# dds.net
KiCad netlist of a schematic drawn in EAGLE
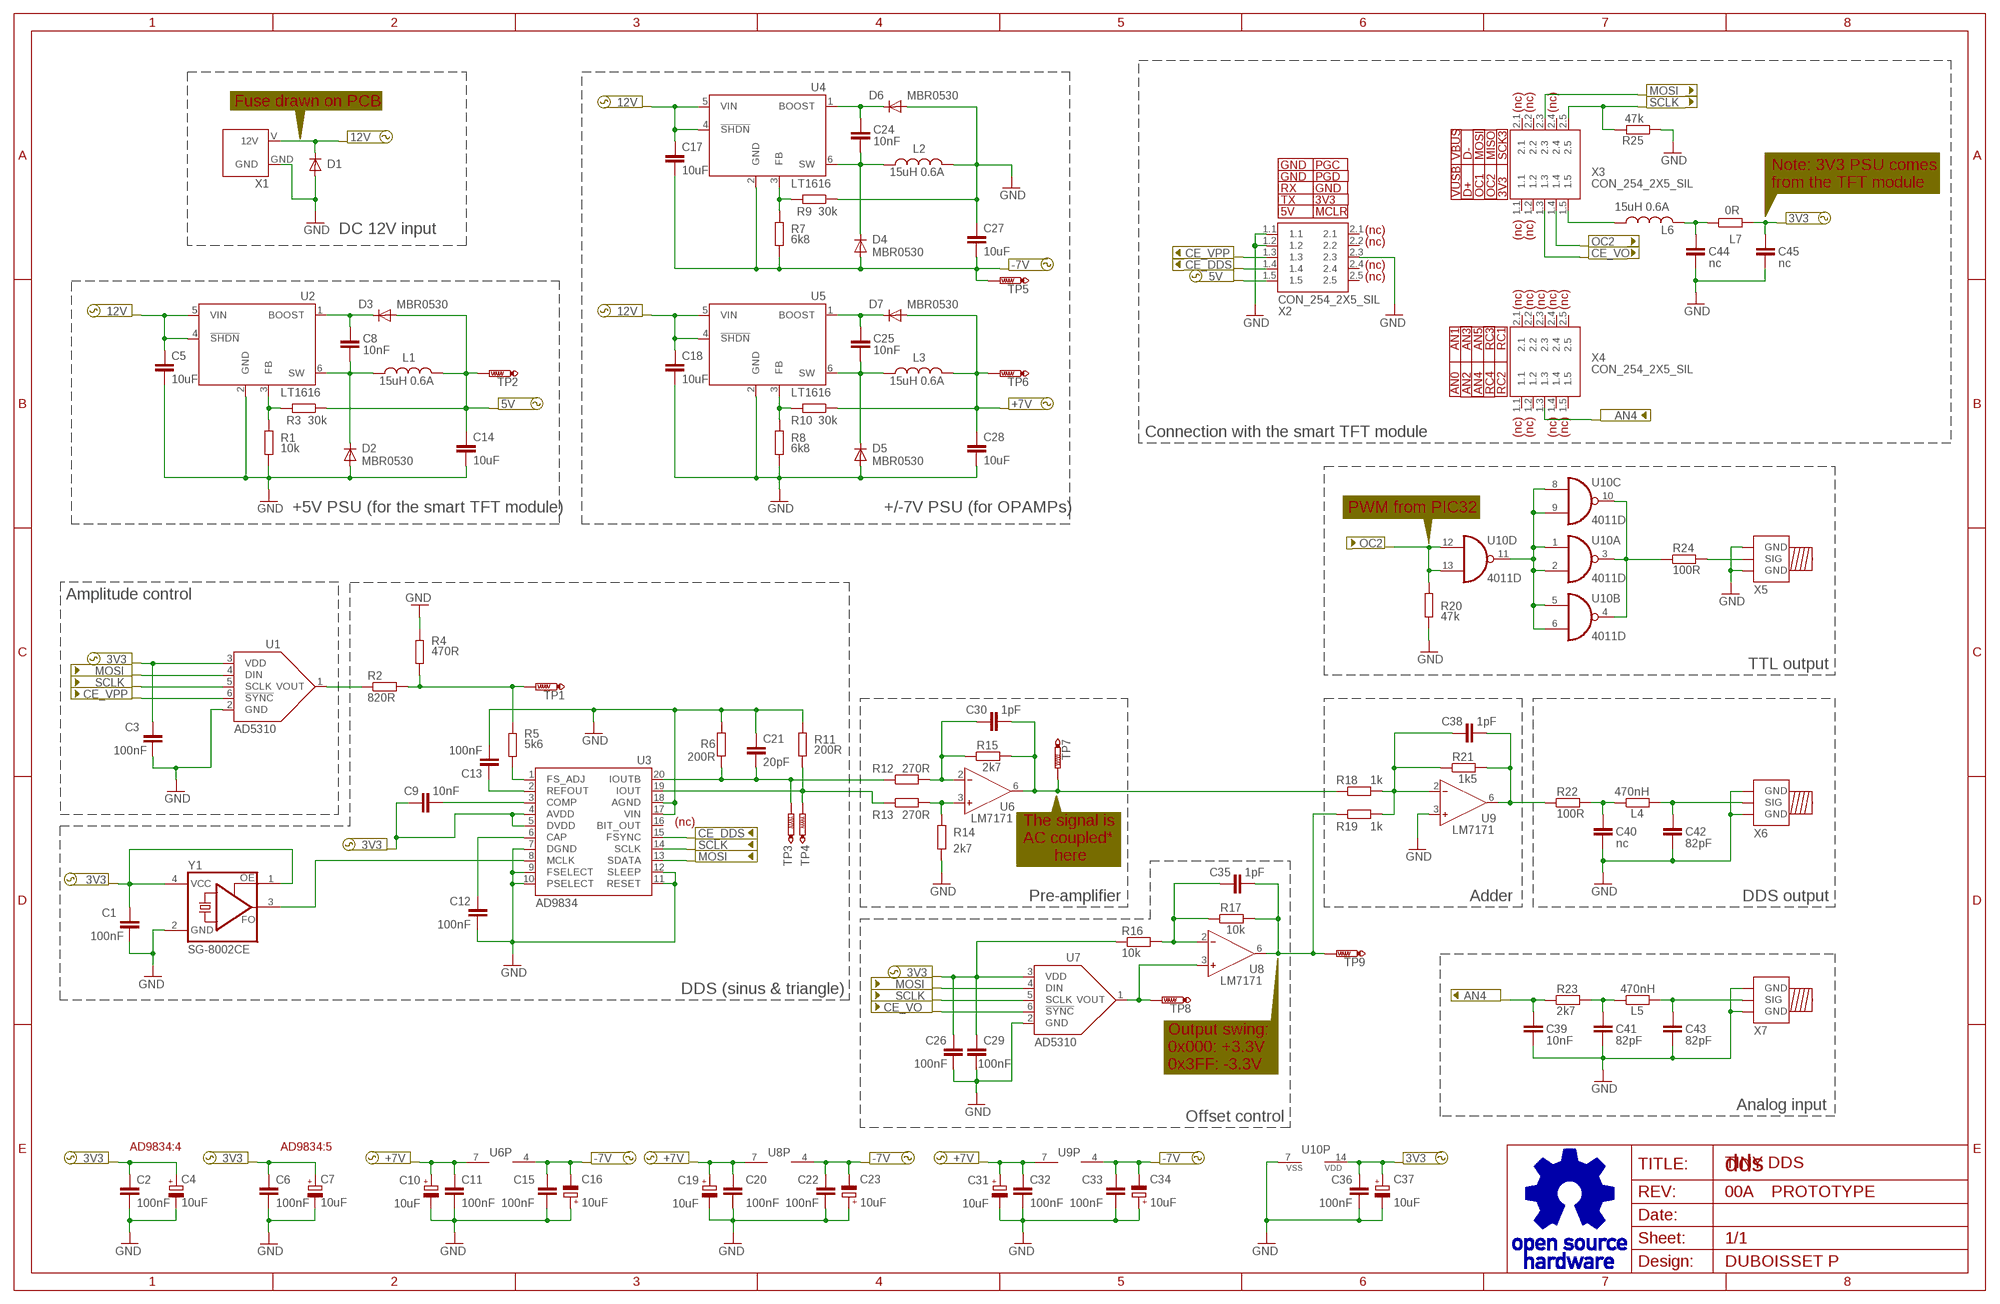
[diagram p0: schematic, sheet 1]

(export (version "E")
  (design (tool "Eeschema 10.0.6"))
  (components
    (comp (ref "C1")
      (value "100nF")
      (footprint "eagle-import:C0603")
      (libsource (lib "eagle-import") (part "C-EUC0603"))
    )
    (comp (ref "C2")
      (value "100nF")
      (footprint "eagle-import:C0603")
      (libsource (lib "eagle-import") (part "C-EUC0603"))
    )
    (comp (ref "C3")
      (value "100nF")
      (footprint "eagle-import:C0603")
      (libsource (lib "eagle-import") (part "C-EUC0603"))
    )
    (comp (ref "C4")
      (value "10uF")
      (footprint "eagle-import:SMC_B")
      (libsource (lib "eagle-import") (part "CPOL-EUSMCB"))
    )
    (comp (ref "C5")
      (value "10uF")
      (footprint "eagle-import:C0805")
      (libsource (lib "eagle-import") (part "C-EUC0805"))
    )
    (comp (ref "C6")
      (value "100nF")
      (footprint "eagle-import:C0603")
      (libsource (lib "eagle-import") (part "C-EUC0603"))
    )
    (comp (ref "C7")
      (value "10uF")
      (footprint "eagle-import:SMC_B")
      (libsource (lib "eagle-import") (part "CPOL-EUSMCB"))
    )
    (comp (ref "C8")
      (value "10nF")
      (footprint "eagle-import:C0603")
      (libsource (lib "eagle-import") (part "C-EUC0603"))
    )
    (comp (ref "C9")
      (value "10nF")
      (footprint "eagle-import:C0603")
      (libsource (lib "eagle-import") (part "C-EUC0603"))
    )
    (comp (ref "C10")
      (value "10uF")
      (footprint "eagle-import:SMC_B")
      (libsource (lib "eagle-import") (part "CPOL-EUSMCB"))
    )
    (comp (ref "C11")
      (value "100nF")
      (footprint "eagle-import:C0603")
      (libsource (lib "eagle-import") (part "C-EUC0603"))
    )
    (comp (ref "C12")
      (value "100nF")
      (footprint "eagle-import:C0603")
      (libsource (lib "eagle-import") (part "C-EUC0603"))
    )
    (comp (ref "C13")
      (value "100nF")
      (footprint "eagle-import:C0603")
      (libsource (lib "eagle-import") (part "C-EUC0603"))
    )
    (comp (ref "C14")
      (value "10uF")
      (footprint "eagle-import:C0805")
      (libsource (lib "eagle-import") (part "C-EUC0805"))
    )
    (comp (ref "C15")
      (value "100nF")
      (footprint "eagle-import:C0603")
      (libsource (lib "eagle-import") (part "C-EUC0603"))
    )
    (comp (ref "C16")
      (value "10uF")
      (footprint "eagle-import:SMC_B")
      (libsource (lib "eagle-import") (part "CPOL-EUSMCB"))
    )
    (comp (ref "C17")
      (value "10uF")
      (footprint "eagle-import:C0805")
      (libsource (lib "eagle-import") (part "C-EUC0805"))
    )
    (comp (ref "C18")
      (value "10uF")
      (footprint "eagle-import:C0805")
      (libsource (lib "eagle-import") (part "C-EUC0805"))
    )
    (comp (ref "C19")
      (value "10uF")
      (footprint "eagle-import:SMC_B")
      (libsource (lib "eagle-import") (part "CPOL-EUSMCB"))
    )
    (comp (ref "C20")
      (value "100nF")
      (footprint "eagle-import:C0603")
      (libsource (lib "eagle-import") (part "C-EUC0603"))
    )
    (comp (ref "C21")
      (value "20pF")
      (footprint "eagle-import:C0603")
      (libsource (lib "eagle-import") (part "C-EUC0603"))
    )
    (comp (ref "C22")
      (value "100nF")
      (footprint "eagle-import:C0603")
      (libsource (lib "eagle-import") (part "C-EUC0603"))
    )
    (comp (ref "C23")
      (value "10uF")
      (footprint "eagle-import:SMC_B")
      (libsource (lib "eagle-import") (part "CPOL-EUSMCB"))
    )
    (comp (ref "C24")
      (value "10nF")
      (footprint "eagle-import:C0603")
      (libsource (lib "eagle-import") (part "C-EUC0603"))
    )
    (comp (ref "C25")
      (value "10nF")
      (footprint "eagle-import:C0603")
      (libsource (lib "eagle-import") (part "C-EUC0603"))
    )
    (comp (ref "C26")
      (value "100nF")
      (footprint "eagle-import:C0603")
      (libsource (lib "eagle-import") (part "C-EUC0603"))
    )
    (comp (ref "C27")
      (value "10uF")
      (footprint "eagle-import:C0805")
      (libsource (lib "eagle-import") (part "C-EUC0805"))
    )
    (comp (ref "C28")
      (value "10uF")
      (footprint "eagle-import:C0805")
      (libsource (lib "eagle-import") (part "C-EUC0805"))
    )
    (comp (ref "C29")
      (value "100nF")
      (footprint "eagle-import:C0603")
      (libsource (lib "eagle-import") (part "C-EUC0603"))
    )
    (comp (ref "C30")
      (value "1pF")
      (footprint "eagle-import:C0603")
      (libsource (lib "eagle-import") (part "C-EUC0603"))
    )
    (comp (ref "C31")
      (value "10uF")
      (footprint "eagle-import:SMC_B")
      (libsource (lib "eagle-import") (part "CPOL-EUSMCB"))
    )
    (comp (ref "C32")
      (value "100nF")
      (footprint "eagle-import:C0603")
      (libsource (lib "eagle-import") (part "C-EUC0603"))
    )
    (comp (ref "C33")
      (value "100nF")
      (footprint "eagle-import:C0603")
      (libsource (lib "eagle-import") (part "C-EUC0603"))
    )
    (comp (ref "C34")
      (value "10uF")
      (footprint "eagle-import:SMC_B")
      (libsource (lib "eagle-import") (part "CPOL-EUSMCB"))
    )
    (comp (ref "C35")
      (value "1pF")
      (footprint "eagle-import:C0603")
      (libsource (lib "eagle-import") (part "C-EUC0603"))
    )
    (comp (ref "C36")
      (value "100nF")
      (footprint "eagle-import:C0603")
      (libsource (lib "eagle-import") (part "C-EUC0603"))
    )
    (comp (ref "C37")
      (value "10uF")
      (footprint "eagle-import:SMC_B")
      (libsource (lib "eagle-import") (part "CPOL-EUSMCB"))
    )
    (comp (ref "C38")
      (value "1pF")
      (footprint "eagle-import:C0603")
      (libsource (lib "eagle-import") (part "C-EUC0603"))
    )
    (comp (ref "C39")
      (value "10nF")
      (footprint "eagle-import:C0603")
      (libsource (lib "eagle-import") (part "C-EUC0603"))
    )
    (comp (ref "C40")
      (value "nc")
      (footprint "eagle-import:C0603")
      (libsource (lib "eagle-import") (part "C-EUC0603"))
    )
    (comp (ref "C41")
      (value "82pF")
      (footprint "eagle-import:C0603")
      (libsource (lib "eagle-import") (part "C-EUC0603"))
    )
    (comp (ref "C42")
      (value "82pF")
      (footprint "eagle-import:C0603")
      (libsource (lib "eagle-import") (part "C-EUC0603"))
    )
    (comp (ref "C43")
      (value "82pF")
      (footprint "eagle-import:C0603")
      (libsource (lib "eagle-import") (part "C-EUC0603"))
    )
    (comp (ref "C44")
      (value "nc")
      (footprint "eagle-import:C0603")
      (libsource (lib "eagle-import") (part "C-EUC0603"))
    )
    (comp (ref "C45")
      (value "nc")
      (footprint "eagle-import:C0603")
      (libsource (lib "eagle-import") (part "C-EUC0603"))
    )
    (comp (ref "D1")
      (value "DIODE-SMB")
      (footprint "eagle-import:SMB")
      (libsource (lib "eagle-import") (part "DIODE-SMB"))
    )
    (comp (ref "D2")
      (value "MBR0530")
      (footprint "eagle-import:SOD123")
      (libsource (lib "eagle-import") (part "DIODE-SOD123"))
    )
    (comp (ref "D3")
      (value "MBR0530")
      (footprint "eagle-import:SOD123")
      (libsource (lib "eagle-import") (part "DIODE-SOD123"))
    )
    (comp (ref "D4")
      (value "MBR0530")
      (footprint "eagle-import:SOD123")
      (libsource (lib "eagle-import") (part "DIODE-SOD123"))
    )
    (comp (ref "D5")
      (value "MBR0530")
      (footprint "eagle-import:SOD123")
      (libsource (lib "eagle-import") (part "DIODE-SOD123"))
    )
    (comp (ref "D6")
      (value "MBR0530")
      (footprint "eagle-import:SOD123")
      (libsource (lib "eagle-import") (part "DIODE-SOD123"))
    )
    (comp (ref "D7")
      (value "MBR0530")
      (footprint "eagle-import:SOD123")
      (libsource (lib "eagle-import") (part "DIODE-SOD123"))
    )
    (comp (ref "L1")
      (value "15uH 0.6A")
      (footprint "eagle-import:L5X3")
      (libsource (lib "eagle-import") (part "L_TDK_15UH"))
    )
    (comp (ref "L2")
      (value "15uH 0.6A")
      (footprint "eagle-import:L5X3")
      (libsource (lib "eagle-import") (part "L_TDK_15UH"))
    )
    (comp (ref "L3")
      (value "15uH 0.6A")
      (footprint "eagle-import:L5X3")
      (libsource (lib "eagle-import") (part "L_TDK_15UH"))
    )
    (comp (ref "L4")
      (value "470nH")
      (footprint "eagle-import:R0603")
      (libsource (lib "eagle-import") (part "R-EU_R0603"))
    )
    (comp (ref "L5")
      (value "470nH")
      (footprint "eagle-import:R0603")
      (libsource (lib "eagle-import") (part "R-EU_R0603"))
    )
    (comp (ref "L6")
      (value "15uH 0.6A")
      (footprint "eagle-import:L5X3")
      (libsource (lib "eagle-import") (part "L_TDK_15UH"))
    )
    (comp (ref "L7")
      (value "0R")
      (footprint "eagle-import:R0603")
      (libsource (lib "eagle-import") (part "R-EU_R0603"))
    )
    (comp (ref "R1")
      (value "10k")
      (footprint "eagle-import:R0603")
      (libsource (lib "eagle-import") (part "R-EU_R0603"))
    )
    (comp (ref "R2")
      (value "820R")
      (footprint "eagle-import:R0603")
      (libsource (lib "eagle-import") (part "R-EU_R0603"))
    )
    (comp (ref "R3")
      (value "30k")
      (footprint "eagle-import:R0603")
      (libsource (lib "eagle-import") (part "R-EU_R0603"))
    )
    (comp (ref "R4")
      (value "470R")
      (footprint "eagle-import:R0603")
      (libsource (lib "eagle-import") (part "R-EU_R0603"))
    )
    (comp (ref "R5")
      (value "5k6")
      (footprint "eagle-import:R0603")
      (libsource (lib "eagle-import") (part "R-EU_R0603"))
    )
    (comp (ref "R6")
      (value "200R")
      (footprint "eagle-import:R0603")
      (libsource (lib "eagle-import") (part "R-EU_R0603"))
    )
    (comp (ref "R7")
      (value "6k8")
      (footprint "eagle-import:R0603")
      (libsource (lib "eagle-import") (part "R-EU_R0603"))
    )
    (comp (ref "R8")
      (value "6k8")
      (footprint "eagle-import:R0603")
      (libsource (lib "eagle-import") (part "R-EU_R0603"))
    )
    (comp (ref "R9")
      (value "30k")
      (footprint "eagle-import:R0603")
      (libsource (lib "eagle-import") (part "R-EU_R0603"))
    )
    (comp (ref "R10")
      (value "30k")
      (footprint "eagle-import:R0603")
      (libsource (lib "eagle-import") (part "R-EU_R0603"))
    )
    (comp (ref "R11")
      (value "200R")
      (footprint "eagle-import:R0603")
      (libsource (lib "eagle-import") (part "R-EU_R0603"))
    )
    (comp (ref "R12")
      (value "270R")
      (footprint "eagle-import:R0603")
      (libsource (lib "eagle-import") (part "R-EU_R0603"))
    )
    (comp (ref "R13")
      (value "270R")
      (footprint "eagle-import:R0603")
      (libsource (lib "eagle-import") (part "R-EU_R0603"))
    )
    (comp (ref "R14")
      (value "2k7")
      (footprint "eagle-import:R0603")
      (libsource (lib "eagle-import") (part "R-EU_R0603"))
    )
    (comp (ref "R15")
      (value "2k7")
      (footprint "eagle-import:R0603")
      (libsource (lib "eagle-import") (part "R-EU_R0603"))
    )
    (comp (ref "R16")
      (value "10k")
      (footprint "eagle-import:R0603")
      (libsource (lib "eagle-import") (part "R-EU_R0603"))
    )
    (comp (ref "R17")
      (value "10k")
      (footprint "eagle-import:R0603")
      (libsource (lib "eagle-import") (part "R-EU_R0603"))
    )
    (comp (ref "R18")
      (value "1k")
      (footprint "eagle-import:R0603")
      (libsource (lib "eagle-import") (part "R-EU_R0603"))
    )
    (comp (ref "R19")
      (value "1k")
      (footprint "eagle-import:R0603")
      (libsource (lib "eagle-import") (part "R-EU_R0603"))
    )
    (comp (ref "R20")
      (value "47k")
      (footprint "eagle-import:R0603")
      (libsource (lib "eagle-import") (part "R-EU_R0603"))
    )
    (comp (ref "R21")
      (value "1k5")
      (footprint "eagle-import:R0603")
      (libsource (lib "eagle-import") (part "R-EU_R0603"))
    )
    (comp (ref "R22")
      (value "100R")
      (footprint "eagle-import:R0603")
      (libsource (lib "eagle-import") (part "R-EU_R0603"))
    )
    (comp (ref "R23")
      (value "2k7")
      (footprint "eagle-import:R0603")
      (libsource (lib "eagle-import") (part "R-EU_R0603"))
    )
    (comp (ref "R24")
      (value "100R")
      (footprint "eagle-import:R0603")
      (libsource (lib "eagle-import") (part "R-EU_R0603"))
    )
    (comp (ref "R25")
      (value "47k")
      (footprint "eagle-import:R0603")
      (libsource (lib "eagle-import") (part "R-EU_R0603"))
    )
    (comp (ref "TP1")
      (value "PTR1B1,27")
      (footprint "eagle-import:B1,27")
      (libsource (lib "eagle-import") (part "PTR1B1,27"))
    )
    (comp (ref "TP2")
      (value "PTR1B1,27")
      (footprint "eagle-import:B1,27")
      (libsource (lib "eagle-import") (part "PTR1B1,27"))
    )
    (comp (ref "TP3")
      (value "PTR1B1,27")
      (footprint "eagle-import:B1,27")
      (libsource (lib "eagle-import") (part "PTR1B1,27"))
    )
    (comp (ref "TP4")
      (value "PTR1B1,27")
      (footprint "eagle-import:B1,27")
      (libsource (lib "eagle-import") (part "PTR1B1,27"))
    )
    (comp (ref "TP5")
      (value "PTR1B1,27")
      (footprint "eagle-import:B1,27")
      (libsource (lib "eagle-import") (part "PTR1B1,27"))
    )
    (comp (ref "TP6")
      (value "PTR1B1,27")
      (footprint "eagle-import:B1,27")
      (libsource (lib "eagle-import") (part "PTR1B1,27"))
    )
    (comp (ref "TP7")
      (value "PTR1B1,27")
      (footprint "eagle-import:B1,27")
      (libsource (lib "eagle-import") (part "PTR1B1,27"))
    )
    (comp (ref "TP8")
      (value "PTR1B1,27")
      (footprint "eagle-import:B1,27")
      (libsource (lib "eagle-import") (part "PTR1B1,27"))
    )
    (comp (ref "TP9")
      (value "PTR1B1,27")
      (footprint "eagle-import:B1,27")
      (libsource (lib "eagle-import") (part "PTR1B1,27"))
    )
    (comp (ref "U1")
      (value "AD5310")
      (footprint "eagle-import:SOT23-6")
      (libsource (lib "eagle-import") (part "AD5310"))
    )
    (comp (ref "U2")
      (value "LT1616")
      (footprint "eagle-import:SOT23-6")
      (libsource (lib "eagle-import") (part "LT1616"))
    )
    (comp (ref "U3")
      (value "AD9834")
      (footprint "eagle-import:TSSOP20")
      (libsource (lib "eagle-import") (part "AD9834"))
    )
    (comp (ref "U4")
      (value "LT1616")
      (footprint "eagle-import:SOT23-6")
      (libsource (lib "eagle-import") (part "LT1616"))
    )
    (comp (ref "U5")
      (value "LT1616")
      (footprint "eagle-import:SOT23-6")
      (libsource (lib "eagle-import") (part "LT1616"))
    )
    (comp (ref "U6")
      (value "LM7171")
      (footprint "eagle-import:SO8")
      (fields (field (name "MF") "ALTERA CORPORATION") (field (name "MPN") "AD811JRZ"))
      (libsource (lib "eagle-import") (part "AD811_SO8"))
    )
    (comp (ref "U7")
      (value "AD5310")
      (footprint "eagle-import:SOT23-6")
      (libsource (lib "eagle-import") (part "AD5310"))
    )
    (comp (ref "U8")
      (value "LM7171")
      (footprint "eagle-import:SO8")
      (fields
        (field (name "MF") "ALTERA CORPORATION")
        (field (name "MPN") "AD811JRZ")
        (field (name "MF_1") "ALTERA CORPORATION")
        (field (name "MPN_1") "AD811JRZ")
        (field (name "OC_FARNELL") "unknown")
        (field (name "OC_NEWARK") "82H2980")
      )
      (libsource (lib "eagle-import") (part "AD811_SO8"))
    )
    (comp (ref "U9")
      (value "LM7171")
      (footprint "eagle-import:SO8")
      (fields (field (name "MF") "ALTERA CORPORATION") (field (name "MPN") "AD811JRZ"))
      (libsource (lib "eagle-import") (part "AD811_SO8"))
    )
    (comp (ref "U10")
      (value "4011D")
      (footprint "eagle-import:SO14")
      (libsource (lib "eagle-import") (part "4011D"))
    )
    (comp (ref "X1")
      (value "CON_12V")
      (footprint "eagle-import:CON_12V")
      (libsource (lib "eagle-import") (part "CON_12V"))
    )
    (comp (ref "X2")
      (value "CON_254_2X5_SIL")
      (footprint "eagle-import:2X5_SIL")
      (libsource (lib "eagle-import") (part "CON_254_2X5_SIL"))
    )
    (comp (ref "X3")
      (value "CON_254_2X5_SIL")
      (footprint "eagle-import:2X5_SIL")
      (libsource (lib "eagle-import") (part "CON_254_2X5_SIL"))
    )
    (comp (ref "X4")
      (value "CON_254_2X5_SIL")
      (footprint "eagle-import:2X5_SIL")
      (libsource (lib "eagle-import") (part "CON_254_2X5_SIL"))
    )
    (comp (ref "X5")
      (value "CON_SMA")
      (footprint "eagle-import:SMA_SMD")
      (libsource (lib "eagle-import") (part "CON_SMA"))
    )
    (comp (ref "X6")
      (value "CON_SMA")
      (footprint "eagle-import:SMA_SMD")
      (libsource (lib "eagle-import") (part "CON_SMA"))
    )
    (comp (ref "X7")
      (value "CON_SMA")
      (footprint "eagle-import:SMA_SMD")
      (libsource (lib "eagle-import") (part "CON_SMA"))
    )
    (comp (ref "Y1")
      (value "SG-8002CE")
      (footprint "eagle-import:ASF")
      (libsource (lib "eagle-import") (part "ASF1"))
    )
  )
  (nets
    (net (code "1") (name "/+7V") (class "Default")
      (node (ref "C10") (pin "+") (pinfunction "+_+") (pintype "passive"))
      (node (ref "C11") (pin "1") (pinfunction "1_1") (pintype "passive"))
      (node (ref "C19") (pin "+") (pinfunction "+_+") (pintype "passive"))
      (node (ref "C20") (pin "1") (pinfunction "1_1") (pintype "passive"))
      (node (ref "C28") (pin "1") (pinfunction "1_1") (pintype "passive"))
      (node (ref "C31") (pin "+") (pinfunction "+_+") (pintype "passive"))
      (node (ref "C32") (pin "1") (pinfunction "1_1") (pintype "passive"))
      (node (ref "D7") (pin "A") (pinfunction "A_A") (pintype "passive"))
      (node (ref "L3") (pin "P$2") (pinfunction "P$2_P$2") (pintype "bidirectional"))
      (node (ref "R10") (pin "1") (pinfunction "1_1") (pintype "passive"))
      (node (ref "TP6") (pin "TP") (pinfunction "TP_TP") (pintype "input"))
      (node (ref "U6") (pin "7") (pinfunction "V+_7") (pintype "power_in"))
      (node (ref "U8") (pin "7") (pinfunction "V+_7") (pintype "power_in"))
      (node (ref "U9") (pin "7") (pinfunction "V+_7") (pintype "power_in"))
    )
    (net (code "2") (name "/-7V") (class "Default")
      (node (ref "C15") (pin "1") (pinfunction "1_1") (pintype "passive"))
      (node (ref "C16") (pin "-") (pinfunction "-_-") (pintype "passive"))
      (node (ref "C17") (pin "2") (pinfunction "2_2") (pintype "passive"))
      (node (ref "C22") (pin "1") (pinfunction "1_1") (pintype "passive"))
      (node (ref "C23") (pin "-") (pinfunction "-_-") (pintype "passive"))
      (node (ref "C27") (pin "2") (pinfunction "2_2") (pintype "passive"))
      (node (ref "C33") (pin "1") (pinfunction "1_1") (pintype "passive"))
      (node (ref "C34") (pin "-") (pinfunction "-_-") (pintype "passive"))
      (node (ref "D4") (pin "A") (pinfunction "A_A") (pintype "passive"))
      (node (ref "R7") (pin "1") (pinfunction "1_1") (pintype "passive"))
      (node (ref "TP5") (pin "TP") (pinfunction "TP_TP") (pintype "input"))
      (node (ref "U4") (pin "2") (pinfunction "GND_2") (pintype "bidirectional"))
      (node (ref "U6") (pin "4") (pinfunction "V-_4") (pintype "power_in"))
      (node (ref "U8") (pin "4") (pinfunction "V-_4") (pintype "power_in"))
      (node (ref "U9") (pin "4") (pinfunction "V-_4") (pintype "power_in"))
    )
    (net (code "3") (name "/3V3") (class "Default")
      (node (ref "C1") (pin "1") (pinfunction "1_1") (pintype "passive"))
      (node (ref "C2") (pin "1") (pinfunction "1_1") (pintype "passive"))
      (node (ref "C26") (pin "1") (pinfunction "1_1") (pintype "passive"))
      (node (ref "C29") (pin "1") (pinfunction "1_1") (pintype "passive"))
      (node (ref "C3") (pin "1") (pinfunction "1_1") (pintype "passive"))
      (node (ref "C36") (pin "1") (pinfunction "1_1") (pintype "passive"))
      (node (ref "C37") (pin "+") (pinfunction "+_+") (pintype "passive"))
      (node (ref "C4") (pin "+") (pinfunction "+_+") (pintype "passive"))
      (node (ref "C45") (pin "1") (pinfunction "1_1") (pintype "passive"))
      (node (ref "C6") (pin "1") (pinfunction "1_1") (pintype "passive"))
      (node (ref "C7") (pin "+") (pinfunction "+_+") (pintype "passive"))
      (node (ref "C9") (pin "2") (pinfunction "2_2") (pintype "passive"))
      (node (ref "L7") (pin "2") (pinfunction "2_2") (pintype "passive"))
      (node (ref "R16") (pin "1") (pinfunction "1_1") (pintype "passive"))
      (node (ref "U1") (pin "3") (pinfunction "VDD_3") (pintype "bidirectional"))
      (node (ref "U10") (pin "14") (pinfunction "VDD_14") (pintype "power_in"))
      (node (ref "U3") (pin "4") (pinfunction "AVDD_4") (pintype "bidirectional"))
      (node (ref "U3") (pin "5") (pinfunction "DVDD_5") (pintype "bidirectional"))
      (node (ref "U7") (pin "3") (pinfunction "VDD_3") (pintype "bidirectional"))
      (node (ref "Y1") (pin "1") (pinfunction "OE_1") (pintype "input"))
      (node (ref "Y1") (pin "4") (pinfunction "VCC_4") (pintype "power_in"))
    )
    (net (code "4") (name "/5V") (class "Default")
      (node (ref "C14") (pin "1") (pinfunction "1_1") (pintype "passive"))
      (node (ref "D3") (pin "A") (pinfunction "A_A") (pintype "passive"))
      (node (ref "L1") (pin "P$2") (pinfunction "P$2_P$2") (pintype "bidirectional"))
      (node (ref "R3") (pin "1") (pinfunction "1_1") (pintype "passive"))
      (node (ref "TP2") (pin "TP") (pinfunction "TP_TP") (pintype "input"))
      (node (ref "X2") (pin "1.5") (pinfunction "1.5_1.5") (pintype "bidirectional"))
    )
    (net (code "5") (name "/12V") (class "Default")
      (node (ref "C17") (pin "1") (pinfunction "1_1") (pintype "passive"))
      (node (ref "C18") (pin "1") (pinfunction "1_1") (pintype "passive"))
      (node (ref "C5") (pin "1") (pinfunction "1_1") (pintype "passive"))
      (node (ref "D1") (pin "C") (pinfunction "C_C") (pintype "passive"))
      (node (ref "U2") (pin "4") (pinfunction "~{SHDN}_4") (pintype "bidirectional"))
      (node (ref "U2") (pin "5") (pinfunction "VIN_5") (pintype "bidirectional"))
      (node (ref "U4") (pin "4") (pinfunction "~{SHDN}_4") (pintype "bidirectional"))
      (node (ref "U4") (pin "5") (pinfunction "VIN_5") (pintype "bidirectional"))
      (node (ref "U5") (pin "4") (pinfunction "~{SHDN}_4") (pintype "bidirectional"))
      (node (ref "U5") (pin "5") (pinfunction "VIN_5") (pintype "bidirectional"))
      (node (ref "X1") (pin "V") (pinfunction "12V_V") (pintype "bidirectional"))
    )
    (net (code "6") (name "/AN4") (class "Default")
      (node (ref "C39") (pin "1") (pinfunction "1_1") (pintype "passive"))
      (node (ref "R23") (pin "1") (pinfunction "1_1") (pintype "passive"))
      (node (ref "X4") (pin "1.3") (pinfunction "1.3_1.3") (pintype "bidirectional"))
    )
    (net (code "7") (name "/CE_DDS") (class "Default")
      (node (ref "U3") (pin "15") (pinfunction "FSYNC_15") (pintype "bidirectional"))
      (node (ref "X2") (pin "1.4") (pinfunction "1.4_1.4") (pintype "bidirectional"))
    )
    (net (code "8") (name "/CE_VO") (class "Default")
      (node (ref "U7") (pin "6") (pinfunction "~{SYNC}_6") (pintype "bidirectional"))
      (node (ref "X3") (pin "1.3") (pinfunction "1.3_1.3") (pintype "bidirectional"))
    )
    (net (code "9") (name "/CE_VPP") (class "Default")
      (node (ref "U1") (pin "6") (pinfunction "~{SYNC}_6") (pintype "bidirectional"))
      (node (ref "X2") (pin "1.3") (pinfunction "1.3_1.3") (pintype "bidirectional"))
    )
    (net (code "10") (name "/MOSI") (class "Default")
      (node (ref "U1") (pin "4") (pinfunction "DIN_4") (pintype "bidirectional"))
      (node (ref "U3") (pin "13") (pinfunction "SDATA_13") (pintype "bidirectional"))
      (node (ref "U7") (pin "4") (pinfunction "DIN_4") (pintype "bidirectional"))
      (node (ref "X3") (pin "2.3") (pinfunction "2.3_2.3") (pintype "bidirectional"))
    )
    (net (code "11") (name "/OC2") (class "Default")
      (node (ref "R20") (pin "2") (pinfunction "2_2") (pintype "passive"))
      (node (ref "U10") (pin "12") (pinfunction "I0_12") (pintype "input"))
      (node (ref "U10") (pin "13") (pinfunction "I1_13") (pintype "input"))
      (node (ref "X3") (pin "1.4") (pinfunction "1.4_1.4") (pintype "bidirectional"))
    )
    (net (code "12") (name "/SCLK") (class "Default")
      (node (ref "R25") (pin "2") (pinfunction "2_2") (pintype "passive"))
      (node (ref "U1") (pin "5") (pinfunction "SCLK_5") (pintype "bidirectional"))
      (node (ref "U3") (pin "14") (pinfunction "SCLK_14") (pintype "bidirectional"))
      (node (ref "U7") (pin "5") (pinfunction "SCLK_5") (pintype "bidirectional"))
      (node (ref "X3") (pin "2.5") (pinfunction "2.5_2.5") (pintype "bidirectional"))
    )
    (net (code "13") (name "GND") (class "Default")
      (node (ref "C1") (pin "2") (pinfunction "2_2") (pintype "passive"))
      (node (ref "C10") (pin "-") (pinfunction "-_-") (pintype "passive"))
      (node (ref "C11") (pin "2") (pinfunction "2_2") (pintype "passive"))
      (node (ref "C12") (pin "2") (pinfunction "2_2") (pintype "passive"))
      (node (ref "C13") (pin "2") (pinfunction "2_2") (pintype "passive"))
      (node (ref "C14") (pin "2") (pinfunction "2_2") (pintype "passive"))
      (node (ref "C15") (pin "2") (pinfunction "2_2") (pintype "passive"))
      (node (ref "C16") (pin "+") (pinfunction "+_+") (pintype "passive"))
      (node (ref "C18") (pin "2") (pinfunction "2_2") (pintype "passive"))
      (node (ref "C19") (pin "-") (pinfunction "-_-") (pintype "passive"))
      (node (ref "C2") (pin "2") (pinfunction "2_2") (pintype "passive"))
      (node (ref "C20") (pin "2") (pinfunction "2_2") (pintype "passive"))
      (node (ref "C21") (pin "1") (pinfunction "1_1") (pintype "passive"))
      (node (ref "C22") (pin "2") (pinfunction "2_2") (pintype "passive"))
      (node (ref "C23") (pin "+") (pinfunction "+_+") (pintype "passive"))
      (node (ref "C26") (pin "2") (pinfunction "2_2") (pintype "passive"))
      (node (ref "C27") (pin "1") (pinfunction "1_1") (pintype "passive"))
      (node (ref "C28") (pin "2") (pinfunction "2_2") (pintype "passive"))
      (node (ref "C29") (pin "2") (pinfunction "2_2") (pintype "passive"))
      (node (ref "C3") (pin "2") (pinfunction "2_2") (pintype "passive"))
      (node (ref "C31") (pin "-") (pinfunction "-_-") (pintype "passive"))
      (node (ref "C32") (pin "2") (pinfunction "2_2") (pintype "passive"))
      (node (ref "C33") (pin "2") (pinfunction "2_2") (pintype "passive"))
      (node (ref "C34") (pin "+") (pinfunction "+_+") (pintype "passive"))
      (node (ref "C36") (pin "2") (pinfunction "2_2") (pintype "passive"))
      (node (ref "C37") (pin "-") (pinfunction "-_-") (pintype "passive"))
      (node (ref "C39") (pin "2") (pinfunction "2_2") (pintype "passive"))
      (node (ref "C4") (pin "-") (pinfunction "-_-") (pintype "passive"))
      (node (ref "C40") (pin "2") (pinfunction "2_2") (pintype "passive"))
      (node (ref "C41") (pin "2") (pinfunction "2_2") (pintype "passive"))
      (node (ref "C42") (pin "2") (pinfunction "2_2") (pintype "passive"))
      (node (ref "C43") (pin "2") (pinfunction "2_2") (pintype "passive"))
      (node (ref "C44") (pin "2") (pinfunction "2_2") (pintype "passive"))
      (node (ref "C45") (pin "2") (pinfunction "2_2") (pintype "passive"))
      (node (ref "C5") (pin "2") (pinfunction "2_2") (pintype "passive"))
      (node (ref "C6") (pin "2") (pinfunction "2_2") (pintype "passive"))
      (node (ref "C7") (pin "-") (pinfunction "-_-") (pintype "passive"))
      (node (ref "D1") (pin "A") (pinfunction "A_A") (pintype "passive"))
      (node (ref "D2") (pin "A") (pinfunction "A_A") (pintype "passive"))
      (node (ref "D5") (pin "A") (pinfunction "A_A") (pintype "passive"))
      (node (ref "D6") (pin "A") (pinfunction "A_A") (pintype "passive"))
      (node (ref "L2") (pin "P$2") (pinfunction "P$2_P$2") (pintype "bidirectional"))
      (node (ref "R1") (pin "1") (pinfunction "1_1") (pintype "passive"))
      (node (ref "R11") (pin "2") (pinfunction "2_2") (pintype "passive"))
      (node (ref "R14") (pin "1") (pinfunction "1_1") (pintype "passive"))
      (node (ref "R20") (pin "1") (pinfunction "1_1") (pintype "passive"))
      (node (ref "R25") (pin "1") (pinfunction "1_1") (pintype "passive"))
      (node (ref "R4") (pin "1") (pinfunction "1_1") (pintype "passive"))
      (node (ref "R6") (pin "2") (pinfunction "2_2") (pintype "passive"))
      (node (ref "R8") (pin "1") (pinfunction "1_1") (pintype "passive"))
      (node (ref "R9") (pin "1") (pinfunction "1_1") (pintype "passive"))
      (node (ref "U1") (pin "2") (pinfunction "GND_2") (pintype "bidirectional"))
      (node (ref "U10") (pin "7") (pinfunction "VSS_7") (pintype "power_in"))
      (node (ref "U2") (pin "2") (pinfunction "GND_2") (pintype "bidirectional"))
      (node (ref "U3") (pin "10") (pinfunction "PSELECT_10") (pintype "bidirectional"))
      (node (ref "U3") (pin "11") (pinfunction "RESET_11") (pintype "bidirectional"))
      (node (ref "U3") (pin "12") (pinfunction "SLEEP_12") (pintype "bidirectional"))
      (node (ref "U3") (pin "17") (pinfunction "VIN_17") (pintype "bidirectional"))
      (node (ref "U3") (pin "18") (pinfunction "AGND_18") (pintype "bidirectional"))
      (node (ref "U3") (pin "7") (pinfunction "DGND_7") (pintype "bidirectional"))
      (node (ref "U3") (pin "9") (pinfunction "FSELECT_9") (pintype "bidirectional"))
      (node (ref "U5") (pin "2") (pinfunction "GND_2") (pintype "bidirectional"))
      (node (ref "U7") (pin "2") (pinfunction "GND_2") (pintype "bidirectional"))
      (node (ref "U9") (pin "3") (pinfunction "IN+_3") (pintype "input"))
      (node (ref "X1") (pin "GND") (pinfunction "GND_GND") (pintype "bidirectional"))
      (node (ref "X2") (pin "1.1") (pinfunction "1.1_1.1") (pintype "bidirectional"))
      (node (ref "X2") (pin "1.2") (pinfunction "1.2_1.2") (pintype "bidirectional"))
      (node (ref "X2") (pin "2.3") (pinfunction "2.3_2.3") (pintype "bidirectional"))
      (node (ref "X5") (pin "GND@1") (pinfunction "GND_GND@1") (pintype "bidirectional"))
      (node (ref "X5") (pin "GND@2") (pinfunction "GND_GND@2") (pintype "bidirectional"))
      (node (ref "X6") (pin "GND@1") (pinfunction "GND_GND@1") (pintype "bidirectional"))
      (node (ref "X6") (pin "GND@2") (pinfunction "GND_GND@2") (pintype "bidirectional"))
      (node (ref "X7") (pin "GND@1") (pinfunction "GND_GND@1") (pintype "bidirectional"))
      (node (ref "X7") (pin "GND@2") (pinfunction "GND_GND@2") (pintype "bidirectional"))
      (node (ref "Y1") (pin "2") (pinfunction "GND_2") (pintype "power_in"))
    )
    (net (code "14") (name "Net-(C40-Pad1)") (class "Default")
      (node (ref "C40") (pin "1") (pinfunction "1_1") (pintype "passive"))
      (node (ref "L4") (pin "1") (pinfunction "1_1") (pintype "passive"))
      (node (ref "R22") (pin "2") (pinfunction "2_2") (pintype "passive"))
    )
    (net (code "15") (name "Net-(C41-Pad1)") (class "Default")
      (node (ref "C41") (pin "1") (pinfunction "1_1") (pintype "passive"))
      (node (ref "L5") (pin "1") (pinfunction "1_1") (pintype "passive"))
      (node (ref "R23") (pin "2") (pinfunction "2_2") (pintype "passive"))
    )
    (net (code "16") (name "Net-(C42-Pad1)") (class "Default")
      (node (ref "C42") (pin "1") (pinfunction "1_1") (pintype "passive"))
      (node (ref "L4") (pin "2") (pinfunction "2_2") (pintype "passive"))
      (node (ref "X6") (pin "SIG") (pinfunction "SIG_SIG") (pintype "bidirectional"))
    )
    (net (code "17") (name "Net-(C43-Pad1)") (class "Default")
      (node (ref "C43") (pin "1") (pinfunction "1_1") (pintype "passive"))
      (node (ref "L5") (pin "2") (pinfunction "2_2") (pintype "passive"))
      (node (ref "X7") (pin "SIG") (pinfunction "SIG_SIG") (pintype "bidirectional"))
    )
    (net (code "18") (name "Net-(C44-Pad1)") (class "Default")
      (node (ref "C44") (pin "1") (pinfunction "1_1") (pintype "passive"))
      (node (ref "L6") (pin "P$2") (pinfunction "P$2_P$2") (pintype "bidirectional"))
      (node (ref "L7") (pin "1") (pinfunction "1_1") (pintype "passive"))
    )
    (net (code "19") (name "Net-(L6-PadP$1)") (class "Default")
      (node (ref "L6") (pin "P$1") (pinfunction "P$1_P$1") (pintype "bidirectional"))
      (node (ref "X3") (pin "1.5") (pinfunction "1.5_1.5") (pintype "bidirectional"))
    )
    (net (code "20") (name "Net-(R2-Pad2)") (class "Default")
      (node (ref "R2") (pin "2") (pinfunction "2_2") (pintype "passive"))
      (node (ref "R4") (pin "2") (pinfunction "2_2") (pintype "passive"))
      (node (ref "R5") (pin "1") (pinfunction "1_1") (pintype "passive"))
      (node (ref "TP1") (pin "TP") (pinfunction "TP_TP") (pintype "input"))
    )
    (net (code "21") (name "Net-(R24-Pad2)") (class "Default")
      (node (ref "R24") (pin "2") (pinfunction "2_2") (pintype "passive"))
      (node (ref "X5") (pin "SIG") (pinfunction "SIG_SIG") (pintype "bidirectional"))
    )
    (net (code "22") (name "Net-(U1-VOUT)") (class "Default")
      (node (ref "R2") (pin "1") (pinfunction "1_1") (pintype "passive"))
      (node (ref "U1") (pin "1") (pinfunction "VOUT_1") (pintype "bidirectional"))
    )
    (net (code "23") (name "Net-(U2-BOOST)") (class "Default")
      (node (ref "C8") (pin "2") (pinfunction "2_2") (pintype "passive"))
      (node (ref "D3") (pin "C") (pinfunction "C_C") (pintype "passive"))
      (node (ref "U2") (pin "1") (pinfunction "BOOST_1") (pintype "bidirectional"))
    )
    (net (code "24") (name "Net-(U2-FB)") (class "Default")
      (node (ref "R1") (pin "2") (pinfunction "2_2") (pintype "passive"))
      (node (ref "R3") (pin "2") (pinfunction "2_2") (pintype "passive"))
      (node (ref "U2") (pin "3") (pinfunction "FB_3") (pintype "bidirectional"))
    )
    (net (code "25") (name "Net-(U2-SW)") (class "Default")
      (node (ref "C8") (pin "1") (pinfunction "1_1") (pintype "passive"))
      (node (ref "D2") (pin "C") (pinfunction "C_C") (pintype "passive"))
      (node (ref "L1") (pin "P$1") (pinfunction "P$1_P$1") (pintype "bidirectional"))
      (node (ref "U2") (pin "6") (pinfunction "SW_6") (pintype "bidirectional"))
    )
    (net (code "26") (name "Net-(U3-CAP)") (class "Default")
      (node (ref "C12") (pin "1") (pinfunction "1_1") (pintype "passive"))
      (node (ref "U3") (pin "6") (pinfunction "CAP_6") (pintype "bidirectional"))
    )
    (net (code "27") (name "Net-(U3-COMP)") (class "Default")
      (node (ref "C9") (pin "1") (pinfunction "1_1") (pintype "passive"))
      (node (ref "U3") (pin "3") (pinfunction "COMP_3") (pintype "bidirectional"))
    )
    (net (code "28") (name "Net-(U3-FS_ADJ)") (class "Default")
      (node (ref "R5") (pin "2") (pinfunction "2_2") (pintype "passive"))
      (node (ref "U3") (pin "1") (pinfunction "FS_ADJ_1") (pintype "bidirectional"))
    )
    (net (code "29") (name "Net-(U3-IOUT)") (class "Default")
      (node (ref "R11") (pin "1") (pinfunction "1_1") (pintype "passive"))
      (node (ref "R13") (pin "1") (pinfunction "1_1") (pintype "passive"))
      (node (ref "TP4") (pin "TP") (pinfunction "TP_TP") (pintype "input"))
      (node (ref "U3") (pin "19") (pinfunction "IOUT_19") (pintype "bidirectional"))
    )
    (net (code "30") (name "Net-(U3-IOUTB)") (class "Default")
      (node (ref "C21") (pin "2") (pinfunction "2_2") (pintype "passive"))
      (node (ref "R12") (pin "1") (pinfunction "1_1") (pintype "passive"))
      (node (ref "R6") (pin "1") (pinfunction "1_1") (pintype "passive"))
      (node (ref "TP3") (pin "TP") (pinfunction "TP_TP") (pintype "input"))
      (node (ref "U3") (pin "20") (pinfunction "IOUTB_20") (pintype "bidirectional"))
    )
    (net (code "31") (name "Net-(U3-MCLK)") (class "Default")
      (node (ref "U3") (pin "8") (pinfunction "MCLK_8") (pintype "bidirectional"))
      (node (ref "Y1") (pin "3") (pinfunction "FO_3") (pintype "output"))
    )
    (net (code "32") (name "Net-(U3-REFOUT)") (class "Default")
      (node (ref "C13") (pin "1") (pinfunction "1_1") (pintype "passive"))
      (node (ref "U3") (pin "2") (pinfunction "REFOUT_2") (pintype "bidirectional"))
    )
    (net (code "33") (name "Net-(U4-BOOST)") (class "Default")
      (node (ref "C24") (pin "2") (pinfunction "2_2") (pintype "passive"))
      (node (ref "D6") (pin "C") (pinfunction "C_C") (pintype "passive"))
      (node (ref "U4") (pin "1") (pinfunction "BOOST_1") (pintype "bidirectional"))
    )
    (net (code "34") (name "Net-(U4-FB)") (class "Default")
      (node (ref "R7") (pin "2") (pinfunction "2_2") (pintype "passive"))
      (node (ref "R9") (pin "2") (pinfunction "2_2") (pintype "passive"))
      (node (ref "U4") (pin "3") (pinfunction "FB_3") (pintype "bidirectional"))
    )
    (net (code "35") (name "Net-(U4-SW)") (class "Default")
      (node (ref "C24") (pin "1") (pinfunction "1_1") (pintype "passive"))
      (node (ref "D4") (pin "C") (pinfunction "C_C") (pintype "passive"))
      (node (ref "L2") (pin "P$1") (pinfunction "P$1_P$1") (pintype "bidirectional"))
      (node (ref "U4") (pin "6") (pinfunction "SW_6") (pintype "bidirectional"))
    )
    (net (code "36") (name "Net-(U5-BOOST)") (class "Default")
      (node (ref "C25") (pin "2") (pinfunction "2_2") (pintype "passive"))
      (node (ref "D7") (pin "C") (pinfunction "C_C") (pintype "passive"))
      (node (ref "U5") (pin "1") (pinfunction "BOOST_1") (pintype "bidirectional"))
    )
    (net (code "37") (name "Net-(U5-FB)") (class "Default")
      (node (ref "R10") (pin "2") (pinfunction "2_2") (pintype "passive"))
      (node (ref "R8") (pin "2") (pinfunction "2_2") (pintype "passive"))
      (node (ref "U5") (pin "3") (pinfunction "FB_3") (pintype "bidirectional"))
    )
    (net (code "38") (name "Net-(U5-SW)") (class "Default")
      (node (ref "C25") (pin "1") (pinfunction "1_1") (pintype "passive"))
      (node (ref "D5") (pin "C") (pinfunction "C_C") (pintype "passive"))
      (node (ref "L3") (pin "P$1") (pinfunction "P$1_P$1") (pintype "bidirectional"))
      (node (ref "U5") (pin "6") (pinfunction "SW_6") (pintype "bidirectional"))
    )
    (net (code "39") (name "Net-(U6D-IN+)") (class "Default")
      (node (ref "R13") (pin "2") (pinfunction "2_2") (pintype "passive"))
      (node (ref "R14") (pin "2") (pinfunction "2_2") (pintype "passive"))
      (node (ref "U6") (pin "3") (pinfunction "IN+_3") (pintype "input"))
    )
    (net (code "40") (name "Net-(U6D-IN-)") (class "Default")
      (node (ref "C30") (pin "1") (pinfunction "1_1") (pintype "passive"))
      (node (ref "R12") (pin "2") (pinfunction "2_2") (pintype "passive"))
      (node (ref "R15") (pin "1") (pinfunction "1_1") (pintype "passive"))
      (node (ref "U6") (pin "2") (pinfunction "IN-_2") (pintype "input"))
    )
    (net (code "41") (name "Net-(U6D-OUT)") (class "Default")
      (node (ref "C30") (pin "2") (pinfunction "2_2") (pintype "passive"))
      (node (ref "R15") (pin "2") (pinfunction "2_2") (pintype "passive"))
      (node (ref "R18") (pin "1") (pinfunction "1_1") (pintype "passive"))
      (node (ref "TP7") (pin "TP") (pinfunction "TP_TP") (pintype "input"))
      (node (ref "U6") (pin "6") (pinfunction "OUT_6") (pintype "output"))
    )
    (net (code "42") (name "Net-(U7-VOUT)") (class "Default")
      (node (ref "TP8") (pin "TP") (pinfunction "TP_TP") (pintype "input"))
      (node (ref "U7") (pin "1") (pinfunction "VOUT_1") (pintype "bidirectional"))
      (node (ref "U8") (pin "3") (pinfunction "IN+_3") (pintype "input"))
    )
    (net (code "43") (name "Net-(U8D-IN-)") (class "Default")
      (node (ref "C35") (pin "1") (pinfunction "1_1") (pintype "passive"))
      (node (ref "R16") (pin "2") (pinfunction "2_2") (pintype "passive"))
      (node (ref "R17") (pin "1") (pinfunction "1_1") (pintype "passive"))
      (node (ref "U8") (pin "2") (pinfunction "IN-_2") (pintype "input"))
    )
    (net (code "44") (name "Net-(U8D-OUT)") (class "Default")
      (node (ref "C35") (pin "2") (pinfunction "2_2") (pintype "passive"))
      (node (ref "R17") (pin "2") (pinfunction "2_2") (pintype "passive"))
      (node (ref "R19") (pin "1") (pinfunction "1_1") (pintype "passive"))
      (node (ref "TP9") (pin "TP") (pinfunction "TP_TP") (pintype "input"))
      (node (ref "U8") (pin "6") (pinfunction "OUT_6") (pintype "output"))
    )
    (net (code "45") (name "Net-(U9D-IN-)") (class "Default")
      (node (ref "C38") (pin "1") (pinfunction "1_1") (pintype "passive"))
      (node (ref "R18") (pin "2") (pinfunction "2_2") (pintype "passive"))
      (node (ref "R19") (pin "2") (pinfunction "2_2") (pintype "passive"))
      (node (ref "R21") (pin "1") (pinfunction "1_1") (pintype "passive"))
      (node (ref "U9") (pin "2") (pinfunction "IN-_2") (pintype "input"))
    )
    (net (code "46") (name "Net-(U9D-OUT)") (class "Default")
      (node (ref "C38") (pin "2") (pinfunction "2_2") (pintype "passive"))
      (node (ref "R21") (pin "2") (pinfunction "2_2") (pintype "passive"))
      (node (ref "R22") (pin "1") (pinfunction "1_1") (pintype "passive"))
      (node (ref "U9") (pin "6") (pinfunction "OUT_6") (pintype "output"))
    )
    (net (code "47") (name "Net-(U10A-I0)") (class "Default")
      (node (ref "U10") (pin "1") (pinfunction "I0_1") (pintype "input"))
      (node (ref "U10") (pin "11") (pinfunction "O_11") (pintype "output"))
      (node (ref "U10") (pin "2") (pinfunction "I1_2") (pintype "input"))
      (node (ref "U10") (pin "5") (pinfunction "I0_5") (pintype "input"))
      (node (ref "U10") (pin "6") (pinfunction "I1_6") (pintype "input"))
      (node (ref "U10") (pin "8") (pinfunction "I0_8") (pintype "input"))
      (node (ref "U10") (pin "9") (pinfunction "I1_9") (pintype "input"))
    )
    (net (code "48") (name "Net-(U10A-O)") (class "Default")
      (node (ref "R24") (pin "1") (pinfunction "1_1") (pintype "passive"))
      (node (ref "U10") (pin "10") (pinfunction "O_10") (pintype "output"))
      (node (ref "U10") (pin "3") (pinfunction "O_3") (pintype "output"))
      (node (ref "U10") (pin "4") (pinfunction "O_4") (pintype "output"))
    )
    (net (code "49") (name "unconnected-(U3-BIT_OUT-Pad16)") (class "Default")
      (node (ref "U3") (pin "16") (pinfunction "BIT_OUT_16") (pintype "bidirectional"))
    )
    (net (code "50") (name "unconnected-(X2-Pad2.1)") (class "Default")
      (node (ref "X2") (pin "2.1") (pinfunction "2.1_2.1") (pintype "bidirectional"))
    )
    (net (code "51") (name "unconnected-(X2-Pad2.2)") (class "Default")
      (node (ref "X2") (pin "2.2") (pinfunction "2.2_2.2") (pintype "bidirectional"))
    )
    (net (code "52") (name "unconnected-(X2-Pad2.4)") (class "Default")
      (node (ref "X2") (pin "2.4") (pinfunction "2.4_2.4") (pintype "bidirectional"))
    )
    (net (code "53") (name "unconnected-(X2-Pad2.5)") (class "Default")
      (node (ref "X2") (pin "2.5") (pinfunction "2.5_2.5") (pintype "bidirectional"))
    )
    (net (code "54") (name "unconnected-(X3-Pad1.1)") (class "Default")
      (node (ref "X3") (pin "1.1") (pinfunction "1.1_1.1") (pintype "bidirectional"))
    )
    (net (code "55") (name "unconnected-(X3-Pad1.2)") (class "Default")
      (node (ref "X3") (pin "1.2") (pinfunction "1.2_1.2") (pintype "bidirectional"))
    )
    (net (code "56") (name "unconnected-(X3-Pad2.1)") (class "Default")
      (node (ref "X3") (pin "2.1") (pinfunction "2.1_2.1") (pintype "bidirectional"))
    )
    (net (code "57") (name "unconnected-(X3-Pad2.2)") (class "Default")
      (node (ref "X3") (pin "2.2") (pinfunction "2.2_2.2") (pintype "bidirectional"))
    )
    (net (code "58") (name "unconnected-(X3-Pad2.4)") (class "Default")
      (node (ref "X3") (pin "2.4") (pinfunction "2.4_2.4") (pintype "bidirectional"))
    )
    (net (code "59") (name "unconnected-(X4-Pad1.1)") (class "Default")
      (node (ref "X4") (pin "1.1") (pinfunction "1.1_1.1") (pintype "bidirectional"))
    )
    (net (code "60") (name "unconnected-(X4-Pad1.2)") (class "Default")
      (node (ref "X4") (pin "1.2") (pinfunction "1.2_1.2") (pintype "bidirectional"))
    )
    (net (code "61") (name "unconnected-(X4-Pad1.4)") (class "Default")
      (node (ref "X4") (pin "1.4") (pinfunction "1.4_1.4") (pintype "bidirectional"))
    )
    (net (code "62") (name "unconnected-(X4-Pad1.5)") (class "Default")
      (node (ref "X4") (pin "1.5") (pinfunction "1.5_1.5") (pintype "bidirectional"))
    )
    (net (code "63") (name "unconnected-(X4-Pad2.1)") (class "Default")
      (node (ref "X4") (pin "2.1") (pinfunction "2.1_2.1") (pintype "bidirectional"))
    )
    (net (code "64") (name "unconnected-(X4-Pad2.2)") (class "Default")
      (node (ref "X4") (pin "2.2") (pinfunction "2.2_2.2") (pintype "bidirectional"))
    )
    (net (code "65") (name "unconnected-(X4-Pad2.3)") (class "Default")
      (node (ref "X4") (pin "2.3") (pinfunction "2.3_2.3") (pintype "bidirectional"))
    )
    (net (code "66") (name "unconnected-(X4-Pad2.4)") (class "Default")
      (node (ref "X4") (pin "2.4") (pinfunction "2.4_2.4") (pintype "bidirectional"))
    )
    (net (code "67") (name "unconnected-(X4-Pad2.5)") (class "Default")
      (node (ref "X4") (pin "2.5") (pinfunction "2.5_2.5") (pintype "bidirectional"))
    )
  )
)
